# MCPICKUP.net
KiCad netlist of a schematic drawn in EasyEDA
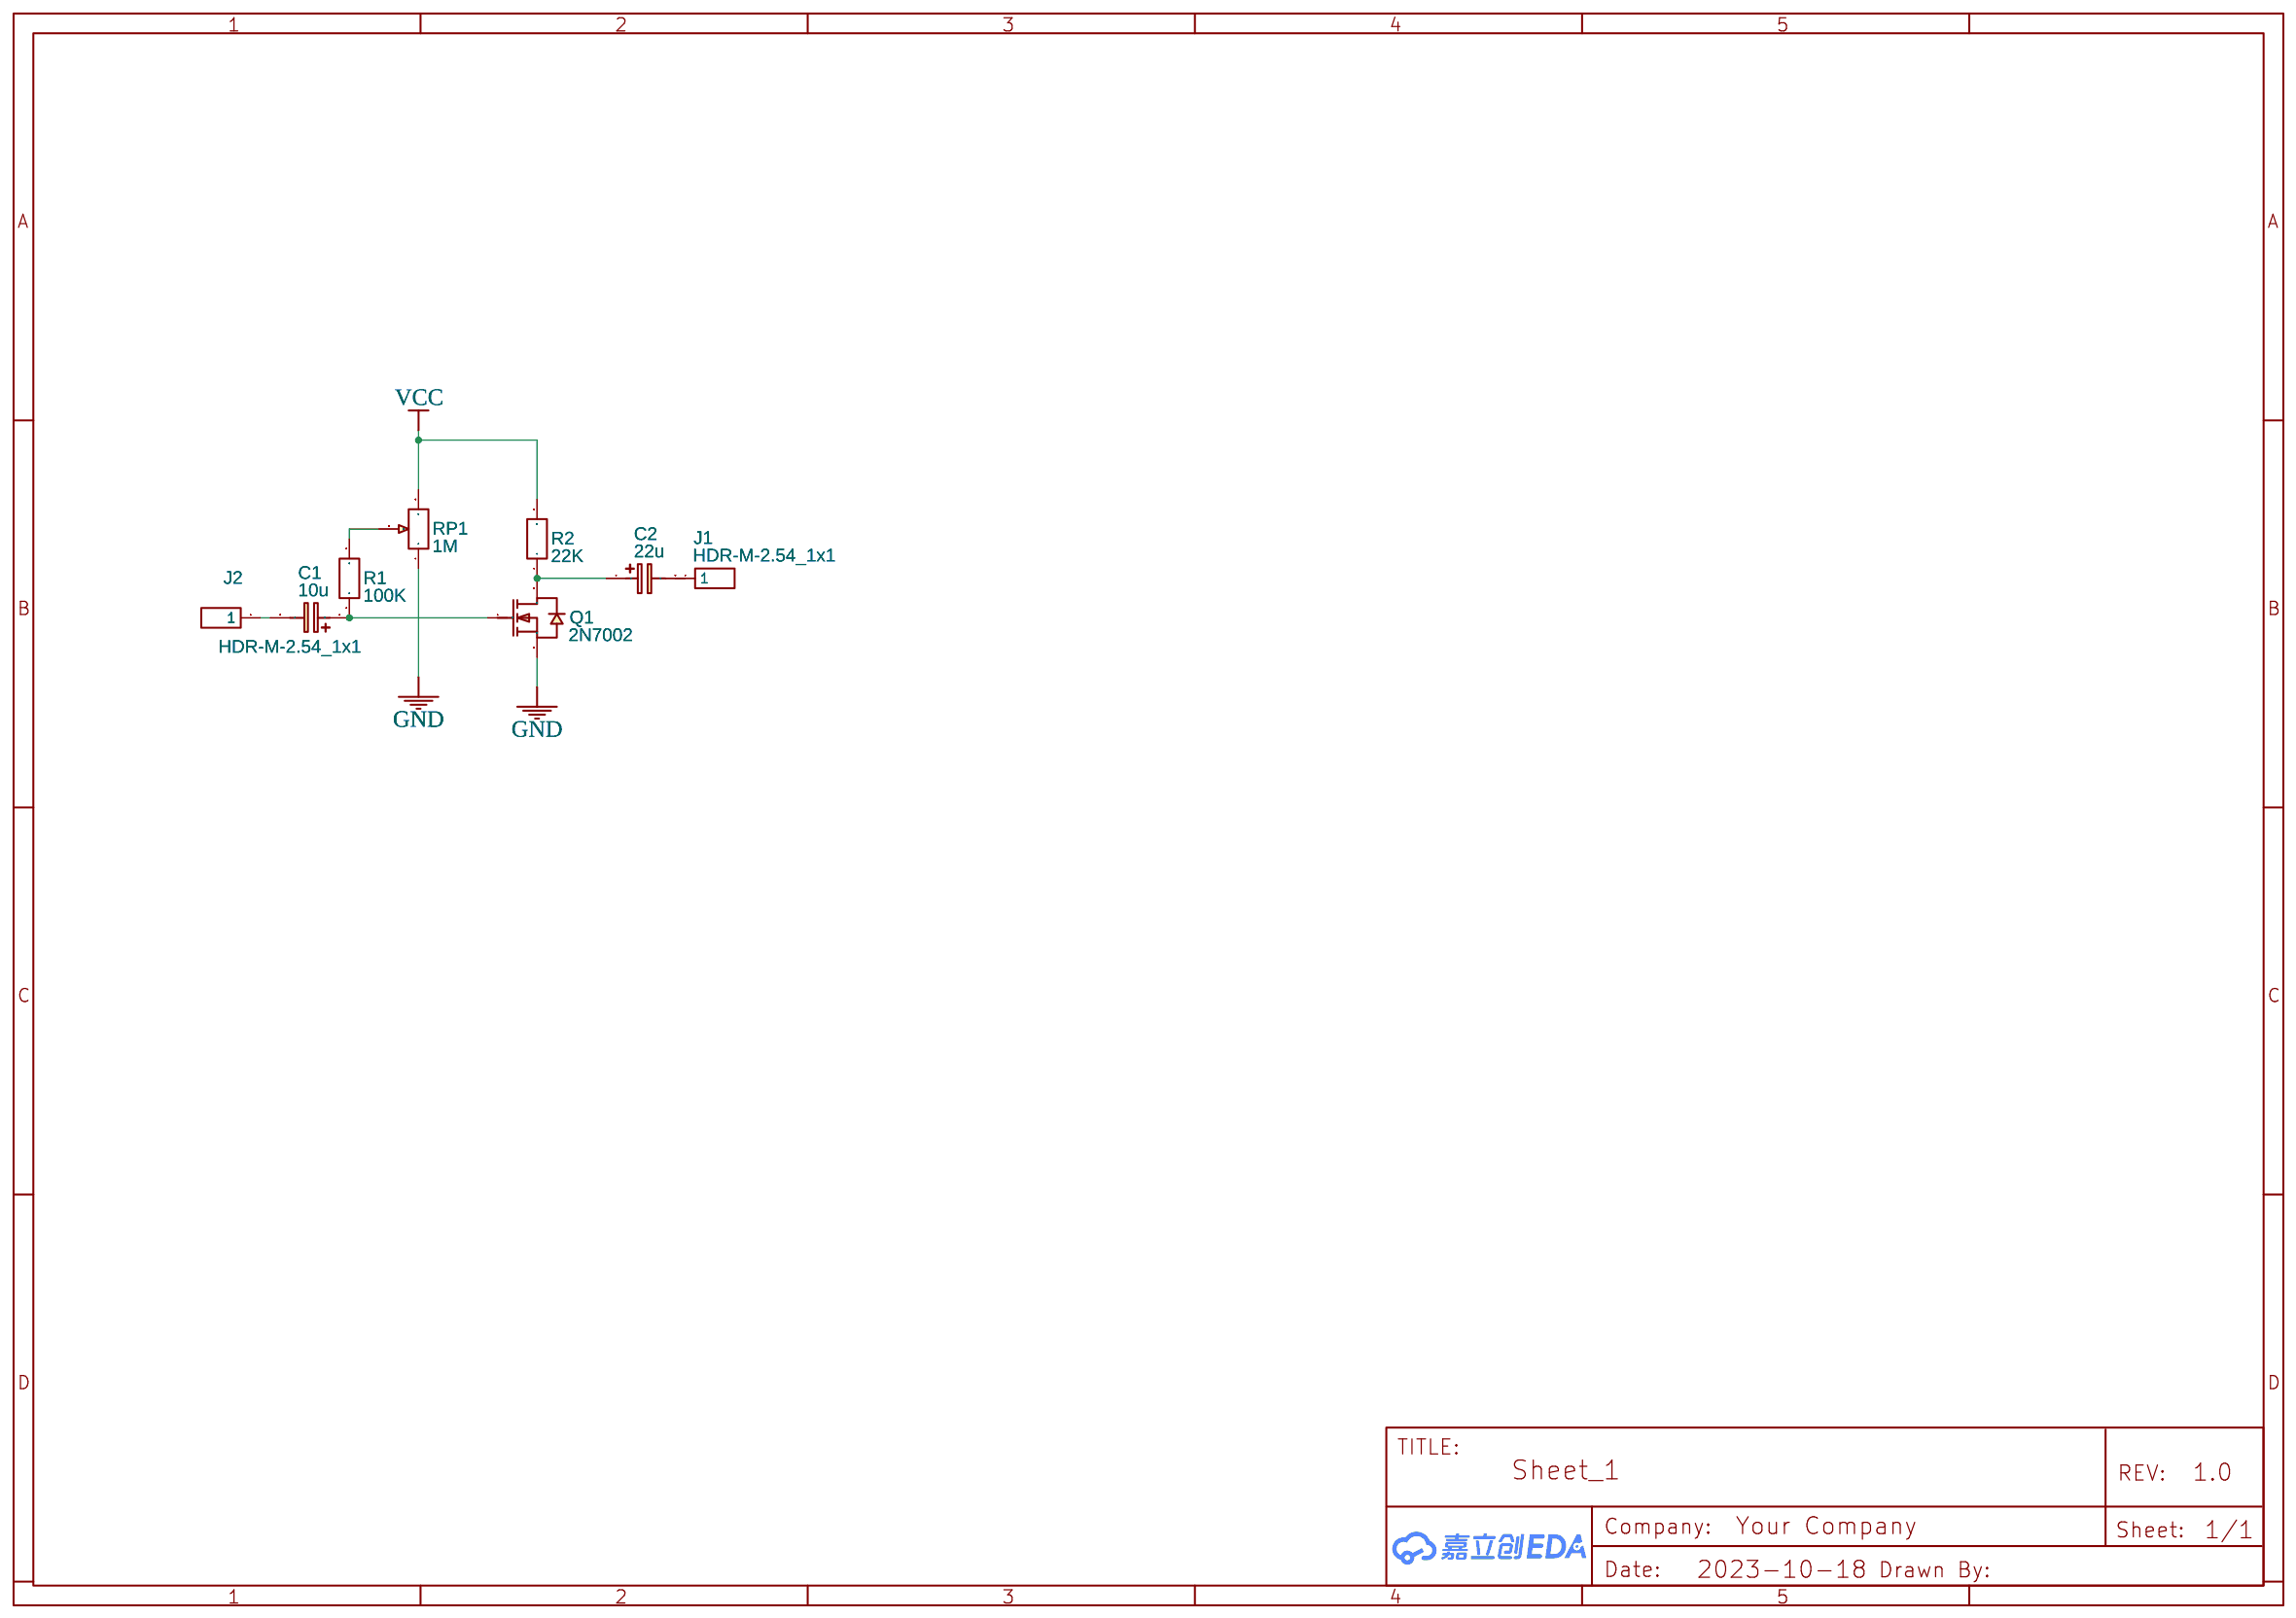
[diagram p0: schematic sheet]

(export (version "E")
  (design (tool "Eeschema 10.0.6"))
  (components
    (comp (ref "C1") (value "10u") (libsource (lib "") (part "C_Tan_SMD_A_EU_1")))
    (comp (ref "C2") (value "22u") (libsource (lib "") (part "C_Tan_SMD_A_EU")))
    (comp (ref "J1")
      (value "HDR-M-2.54_1x1")
      (fields (field (name "BOM_Supplier Part") "C81276"))
      (libsource (lib "") (part "HDR-M-2.54_1x1_1"))
    )
    (comp (ref "J2")
      (value "HDR-M-2.54_1x1")
      (fields (field (name "BOM_Supplier Part") "C81276"))
      (libsource (lib "") (part "HDR-M-2.54_1x1"))
    )
    (comp (ref "Q1")
      (value "2N7002")
      (fields (field (name "BOM_Manufacturer Part") "2N7002,215") (field (name "BOM_Supplier Part") "C65189"))
      (libsource (lib "") (part "2N7002"))
    )
    (comp (ref "R1") (value "100K") (libsource (lib "") (part "R_0603_EU")))
    (comp (ref "R2") (value "22K") (libsource (lib "") (part "R_0603_EU")))
    (comp (ref "RP1") (value "1M") (libsource (lib "") (part "R_3296W_EU")))
  )
  (nets
    (net (code "1") (name "GND") (class "Default")
      (node (ref "Q1") (pin "2") (pinfunction "S_2") (pintype "unspecified"))
      (node (ref "RP1") (pin "1") (pinfunction "1_1") (pintype "input"))
    )
    (net (code "2") (name "Net-(C1-Pad2)") (class "Default")
      (node (ref "C1") (pin "2") (pinfunction "2_2") (pintype "unspecified"))
      (node (ref "J2") (pin "1") (pinfunction "1_1") (pintype "input"))
    )
    (net (code "3") (name "Net-(Q1-D)") (class "Default")
      (node (ref "C2") (pin "1") (pinfunction "1_1") (pintype "unspecified"))
      (node (ref "Q1") (pin "3") (pinfunction "D_3") (pintype "unspecified"))
      (node (ref "R2") (pin "1") (pinfunction "1_1") (pintype "unspecified"))
    )
    (net (code "4") (name "Net-(Q1-G)") (class "Default")
      (node (ref "C1") (pin "1") (pinfunction "1_1") (pintype "unspecified"))
      (node (ref "Q1") (pin "1") (pinfunction "G_1") (pintype "unspecified"))
      (node (ref "R1") (pin "1") (pinfunction "1_1") (pintype "unspecified"))
    )
    (net (code "5") (name "Net-(R1-Pad2)") (class "Default")
      (node (ref "R1") (pin "2") (pinfunction "2_2") (pintype "unspecified"))
      (node (ref "RP1") (pin "2") (pinfunction "2_2") (pintype "input"))
    )
    (net (code "6") (name "VCC") (class "Default")
      (node (ref "R2") (pin "2") (pinfunction "2_2") (pintype "unspecified"))
      (node (ref "RP1") (pin "3") (pinfunction "3_3") (pintype "input"))
    )
    (net (code "7") (name "unconnected-(C2-Pad2)") (class "Default")
      (node (ref "C2") (pin "2") (pinfunction "2_2") (pintype "unspecified"))
    )
    (net (code "8") (name "unconnected-(J1-Pad1)") (class "Default")
      (node (ref "J1") (pin "1") (pinfunction "1_1") (pintype "input"))
    )
  )
)
